# microbutton.net
KiCad netlist of a schematic drawn in EAGLE
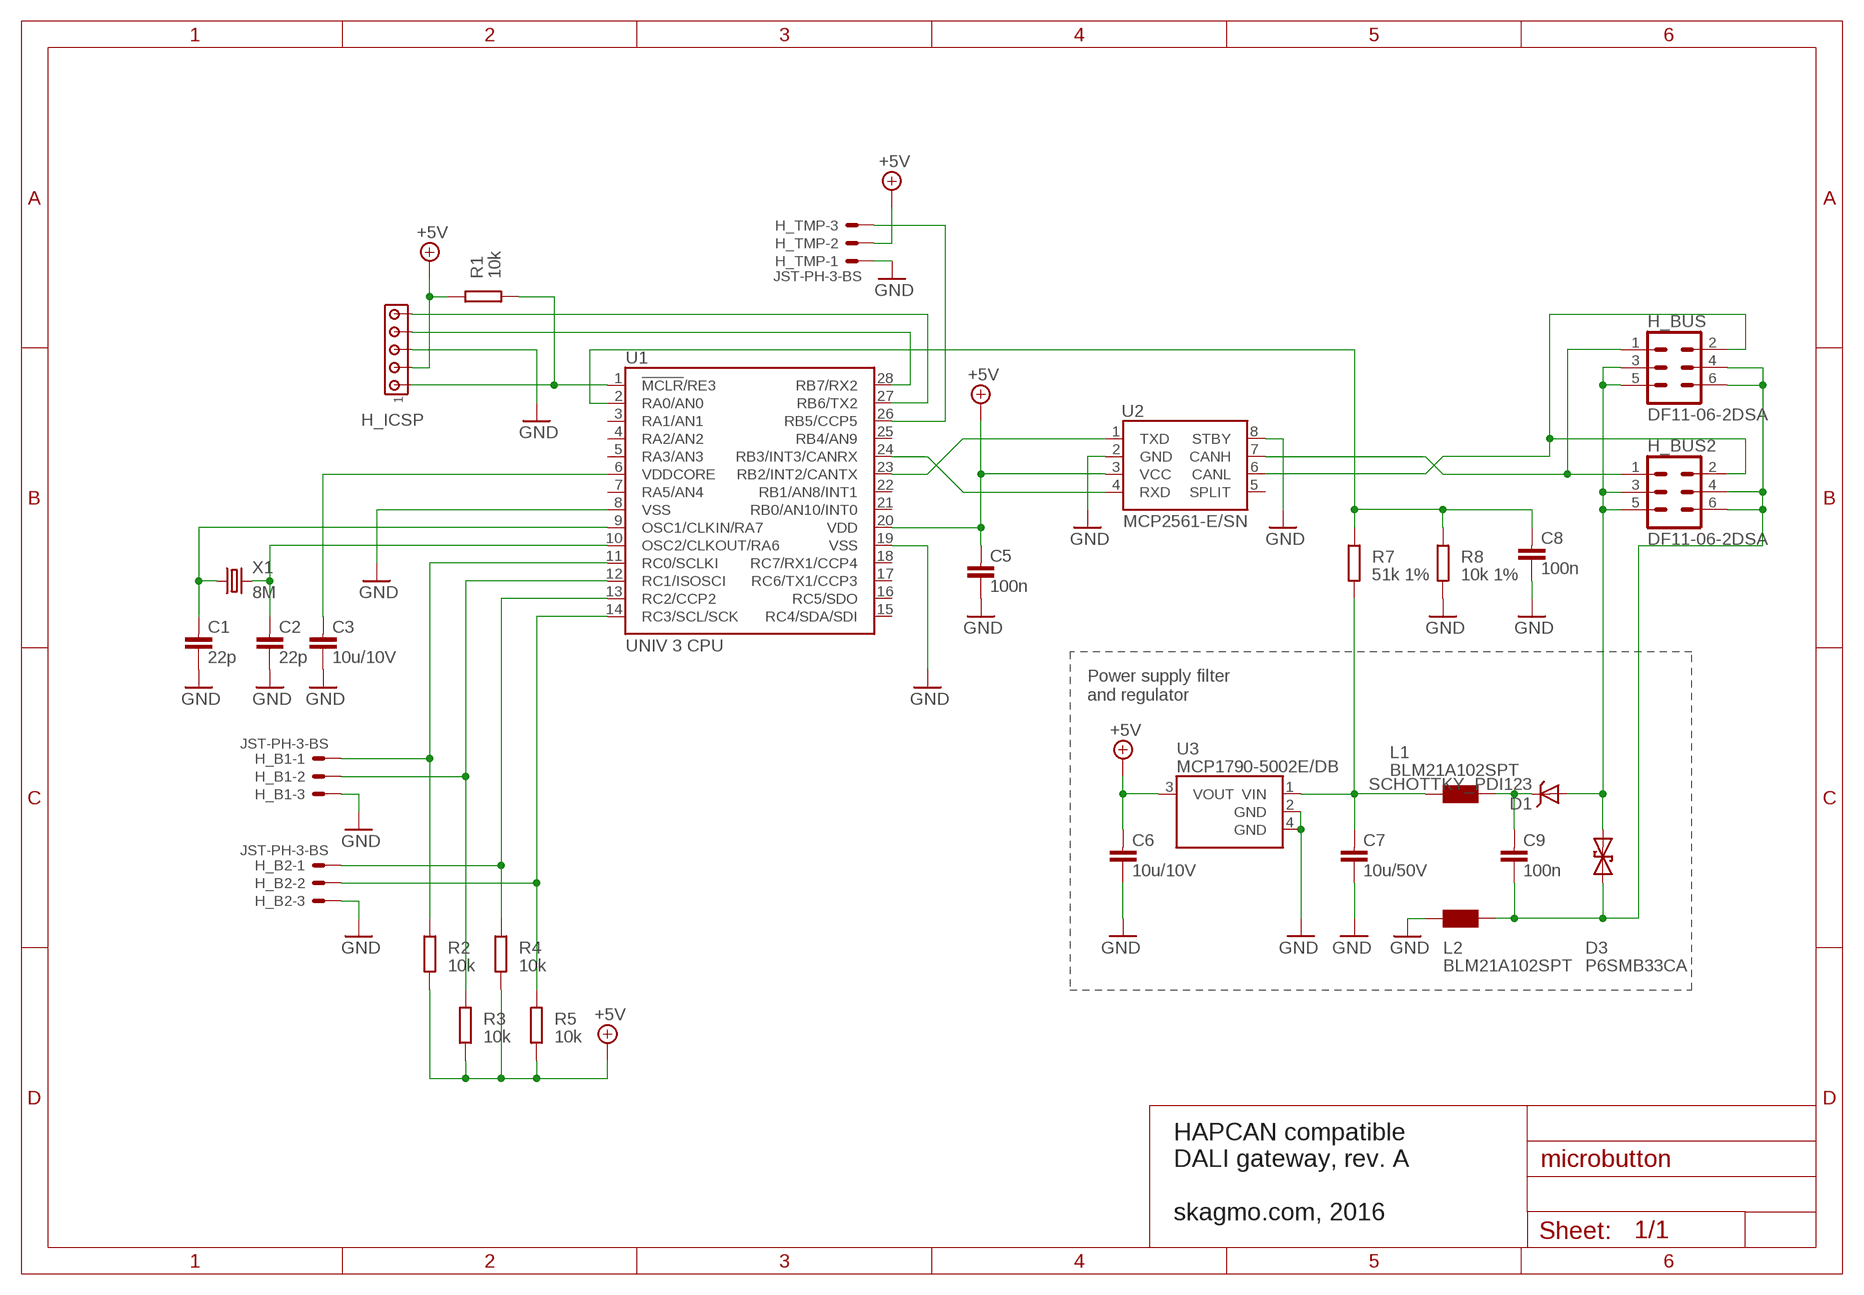
[diagram p0: schematic, sheet 1]

(export (version "E")
  (design (tool "Eeschema 10.0.6"))
  (components
    (comp (ref "C1")
      (value "22p")
      (footprint "eagle-import:0805")
      (libsource (lib "eagle-import") (part "CAPACITOR0805"))
    )
    (comp (ref "C2")
      (value "22p")
      (footprint "eagle-import:0805")
      (libsource (lib "eagle-import") (part "CAPACITOR0805"))
    )
    (comp (ref "C3")
      (value "10u/10V")
      (footprint "eagle-import:0805")
      (libsource (lib "eagle-import") (part "CAPACITOR0805"))
    )
    (comp (ref "C5")
      (value "100n")
      (footprint "eagle-import:0805")
      (libsource (lib "eagle-import") (part "CAPACITOR0805"))
    )
    (comp (ref "C6")
      (value "10u/10V")
      (footprint "eagle-import:0805")
      (libsource (lib "eagle-import") (part "CAPACITOR0805"))
    )
    (comp (ref "C7")
      (value "10u/50V")
      (footprint "eagle-import:1210")
      (libsource (lib "eagle-import") (part "CAPACITOR1210"))
    )
    (comp (ref "C8")
      (value "100n")
      (footprint "eagle-import:0805")
      (libsource (lib "eagle-import") (part "CAPACITOR0805"))
    )
    (comp (ref "C9")
      (value "100n")
      (footprint "eagle-import:0805")
      (libsource (lib "eagle-import") (part "CAPACITOR0805"))
    )
    (comp (ref "D1")
      (value "SCHOTTKY_PDI123")
      (footprint "eagle-import:POWERDI123")
      (libsource (lib "eagle-import") (part "SCHOTTKY_PDI123"))
    )
    (comp (ref "D3")
      (value "P6SMB33CA")
      (footprint "eagle-import:DO-214_TRANSIL2")
      (libsource (lib "eagle-import") (part "DIODE_TRANSIL2"))
    )
    (comp (ref "H_B1")
      (value "JST-PH-3-BS")
      (footprint "eagle-import:B3B-PH-K-S")
      (libsource (lib "eagle-import") (part "JST-PH-3-BS"))
    )
    (comp (ref "H_B2")
      (value "JST-PH-3-BS")
      (footprint "eagle-import:B3B-PH-K-S")
      (libsource (lib "eagle-import") (part "JST-PH-3-BS"))
    )
    (comp (ref "H_BUS")
      (value "DF11-06-2DSA")
      (footprint "eagle-import:DF11-06DP-2DSA")
      (libsource (lib "eagle-import") (part "DF11-06-2DSA"))
    )
    (comp (ref "H_BUS2")
      (value "DF11-06-2DSA")
      (footprint "eagle-import:DF11-06DP-2DSA")
      (libsource (lib "eagle-import") (part "DF11-06-2DSA"))
    )
    (comp (ref "H_ICSP")
      (value "HEADER5")
      (footprint "eagle-import:SIP-5")
      (libsource (lib "eagle-import") (part "HEADER5"))
    )
    (comp (ref "H_TMP")
      (value "JST-PH-3-BS")
      (footprint "eagle-import:B3B-PH-K-S")
      (libsource (lib "eagle-import") (part "JST-PH-3-BS"))
    )
    (comp (ref "L1")
      (value "BLM21A102SPT")
      (footprint "eagle-import:0805")
      (libsource (lib "eagle-import") (part "CHOKE0805"))
    )
    (comp (ref "L2")
      (value "BLM21A102SPT")
      (footprint "eagle-import:0805")
      (libsource (lib "eagle-import") (part "CHOKE0805"))
    )
    (comp (ref "R1")
      (value "10k")
      (footprint "eagle-import:0805")
      (libsource (lib "eagle-import") (part "RESISTOR0805"))
    )
    (comp (ref "R2")
      (value "10k")
      (footprint "eagle-import:0805")
      (libsource (lib "eagle-import") (part "RESISTOR0805"))
    )
    (comp (ref "R3")
      (value "10k")
      (footprint "eagle-import:0805")
      (libsource (lib "eagle-import") (part "RESISTOR0805"))
    )
    (comp (ref "R4")
      (value "10k")
      (footprint "eagle-import:0805")
      (libsource (lib "eagle-import") (part "RESISTOR0805"))
    )
    (comp (ref "R5")
      (value "10k")
      (footprint "eagle-import:0805")
      (libsource (lib "eagle-import") (part "RESISTOR0805"))
    )
    (comp (ref "R7")
      (value "51k 1%")
      (footprint "eagle-import:0805")
      (libsource (lib "eagle-import") (part "RESISTOR0805"))
    )
    (comp (ref "R8")
      (value "10k 1%")
      (footprint "eagle-import:0805")
      (libsource (lib "eagle-import") (part "RESISTOR0805"))
    )
    (comp (ref "U1")
      (value "UNIV 3 CPU")
      (footprint "eagle-import:UNIV3CPU")
      (libsource (lib "eagle-import") (part "UNIV3CPU"))
    )
    (comp (ref "U2")
      (value "MCP2561-E/SN")
      (footprint "eagle-import:SO-08")
      (libsource (lib "eagle-import") (part "MCP2561-E/SN"))
    )
    (comp (ref "U3")
      (value "MCP1790-5002E/DB")
      (footprint "eagle-import:SOT-223")
      (libsource (lib "eagle-import") (part "MCP1790"))
    )
    (comp (ref "X1")
      (value "8M")
      (footprint "eagle-import:TXC-7A")
      (libsource (lib "eagle-import") (part "CRYSTAL_TXC-7A"))
    )
  )
  (nets
    (net (code "1") (name "+5V") (class "Default")
      (node (ref "C5") (pin "1") (pinfunction "1_1") (pintype "passive"))
      (node (ref "C6") (pin "1") (pinfunction "1_1") (pintype "passive"))
      (node (ref "H_ICSP") (pin "2") (pinfunction "2_2") (pintype "passive"))
      (node (ref "H_TMP") (pin "2") (pinfunction "S_2") (pintype "passive"))
      (node (ref "R1") (pin "2") (pinfunction "2_2") (pintype "passive"))
      (node (ref "R2") (pin "1") (pinfunction "1_1") (pintype "passive"))
      (node (ref "R3") (pin "1") (pinfunction "1_1") (pintype "passive"))
      (node (ref "R4") (pin "1") (pinfunction "1_1") (pintype "passive"))
      (node (ref "R5") (pin "1") (pinfunction "1_1") (pintype "passive"))
      (node (ref "U1") (pin "20") (pinfunction "VDD_20") (pintype "bidirectional"))
      (node (ref "U2") (pin "3") (pinfunction "VCC_3") (pintype "bidirectional"))
      (node (ref "U3") (pin "3") (pinfunction "VOUT_3") (pintype "bidirectional"))
    )
    (net (code "2") (name "GND") (class "Default")
      (node (ref "C1") (pin "2") (pinfunction "2_2") (pintype "passive"))
      (node (ref "C2") (pin "2") (pinfunction "2_2") (pintype "passive"))
      (node (ref "C3") (pin "2") (pinfunction "2_2") (pintype "passive"))
      (node (ref "C5") (pin "2") (pinfunction "2_2") (pintype "passive"))
      (node (ref "C6") (pin "2") (pinfunction "2_2") (pintype "passive"))
      (node (ref "C7") (pin "2") (pinfunction "2_2") (pintype "passive"))
      (node (ref "C8") (pin "2") (pinfunction "2_2") (pintype "passive"))
      (node (ref "H_B1") (pin "3") (pinfunction "S_3") (pintype "passive"))
      (node (ref "H_B2") (pin "3") (pinfunction "S_3") (pintype "passive"))
      (node (ref "H_ICSP") (pin "3") (pinfunction "3_3") (pintype "passive"))
      (node (ref "H_TMP") (pin "1") (pinfunction "S_1") (pintype "passive"))
      (node (ref "L2") (pin "1") (pinfunction "1_1") (pintype "passive"))
      (node (ref "R8") (pin "1") (pinfunction "1_1") (pintype "passive"))
      (node (ref "U1") (pin "19") (pinfunction "VSS_19") (pintype "bidirectional"))
      (node (ref "U1") (pin "8") (pinfunction "VSS_8") (pintype "bidirectional"))
      (node (ref "U2") (pin "2") (pinfunction "GND_2") (pintype "bidirectional"))
      (node (ref "U2") (pin "8") (pinfunction "STBY_8") (pintype "bidirectional"))
      (node (ref "U3") (pin "2") (pinfunction "GND_2") (pintype "bidirectional"))
      (node (ref "U3") (pin "4") (pinfunction "GND_4") (pintype "bidirectional"))
    )
    (net (code "3") (name "Net-(C9-Pad1)") (class "Default")
      (node (ref "C9") (pin "1") (pinfunction "1_1") (pintype "passive"))
      (node (ref "D1") (pin "C") (pinfunction "C_C") (pintype "passive"))
      (node (ref "L1") (pin "2") (pinfunction "2_2") (pintype "passive"))
    )
    (net (code "4") (name "Net-(D3-1)") (class "Default")
      (node (ref "C9") (pin "2") (pinfunction "2_2") (pintype "passive"))
      (node (ref "D3") (pin "A") (pinfunction "1_A") (pintype "passive"))
      (node (ref "H_BUS") (pin "4") (pinfunction "4_4") (pintype "passive"))
      (node (ref "H_BUS") (pin "6") (pinfunction "6_6") (pintype "passive"))
      (node (ref "H_BUS2") (pin "4") (pinfunction "4_4") (pintype "passive"))
      (node (ref "H_BUS2") (pin "6") (pinfunction "6_6") (pintype "passive"))
      (node (ref "L2") (pin "2") (pinfunction "2_2") (pintype "passive"))
    )
    (net (code "5") (name "Net-(D3-2)") (class "Default")
      (node (ref "D1") (pin "A") (pinfunction "A_A") (pintype "passive"))
      (node (ref "D3") (pin "C") (pinfunction "2_C") (pintype "passive"))
      (node (ref "H_BUS") (pin "3") (pinfunction "3_3") (pintype "passive"))
      (node (ref "H_BUS") (pin "5") (pinfunction "5_5") (pintype "passive"))
      (node (ref "H_BUS2") (pin "3") (pinfunction "3_3") (pintype "passive"))
      (node (ref "H_BUS2") (pin "5") (pinfunction "5_5") (pintype "passive"))
    )
    (net (code "6") (name "Net-(H_B1A-S)") (class "Default")
      (node (ref "H_B1") (pin "1") (pinfunction "S_1") (pintype "passive"))
      (node (ref "R2") (pin "2") (pinfunction "2_2") (pintype "passive"))
      (node (ref "U1") (pin "11") (pinfunction "RC0/SCLKI_11") (pintype "bidirectional"))
    )
    (net (code "7") (name "Net-(H_B1B-S)") (class "Default")
      (node (ref "H_B1") (pin "2") (pinfunction "S_2") (pintype "passive"))
      (node (ref "R3") (pin "2") (pinfunction "2_2") (pintype "passive"))
      (node (ref "U1") (pin "12") (pinfunction "RC1/ISOSCI_12") (pintype "bidirectional"))
    )
    (net (code "8") (name "Net-(H_B2A-S)") (class "Default")
      (node (ref "H_B2") (pin "1") (pinfunction "S_1") (pintype "passive"))
      (node (ref "R4") (pin "2") (pinfunction "2_2") (pintype "passive"))
      (node (ref "U1") (pin "13") (pinfunction "RC2/CCP2_13") (pintype "bidirectional"))
    )
    (net (code "9") (name "Net-(H_B2B-S)") (class "Default")
      (node (ref "H_B2") (pin "2") (pinfunction "S_2") (pintype "passive"))
      (node (ref "R5") (pin "2") (pinfunction "2_2") (pintype "passive"))
      (node (ref "U1") (pin "14") (pinfunction "RC3/SCL/SCK_14") (pintype "bidirectional"))
    )
    (net (code "10") (name "Net-(H_TMPC-S)") (class "Default")
      (node (ref "H_TMP") (pin "3") (pinfunction "S_3") (pintype "passive"))
      (node (ref "U1") (pin "26") (pinfunction "RB5/CCP5_26") (pintype "bidirectional"))
    )
    (net (code "11") (name "Net-(U1-OSC1{slash}CLKIN{slash}RA7)") (class "Default")
      (node (ref "C1") (pin "1") (pinfunction "1_1") (pintype "passive"))
      (node (ref "U1") (pin "9") (pinfunction "OSC1/CLKIN/RA7_9") (pintype "bidirectional"))
      (node (ref "X1") (pin "1") (pinfunction "1_1") (pintype "passive"))
    )
    (net (code "12") (name "Net-(U1-OSC2{slash}CLKOUT{slash}RA6)") (class "Default")
      (node (ref "C2") (pin "1") (pinfunction "1_1") (pintype "passive"))
      (node (ref "U1") (pin "10") (pinfunction "OSC2/CLKOUT/RA6_10") (pintype "bidirectional"))
      (node (ref "X1") (pin "2") (pinfunction "2_2") (pintype "passive"))
    )
    (net (code "13") (name "Net-(U1-RA0{slash}AN0)") (class "Default")
      (node (ref "C8") (pin "1") (pinfunction "1_1") (pintype "passive"))
      (node (ref "R7") (pin "2") (pinfunction "2_2") (pintype "passive"))
      (node (ref "R8") (pin "2") (pinfunction "2_2") (pintype "passive"))
      (node (ref "U1") (pin "2") (pinfunction "RA0/AN0_2") (pintype "bidirectional"))
    )
    (net (code "14") (name "Net-(U1-RB2{slash}INT2{slash}CANTX)") (class "Default")
      (node (ref "U1") (pin "23") (pinfunction "RB2/INT2/CANTX_23") (pintype "bidirectional"))
      (node (ref "U2") (pin "1") (pinfunction "TXD_1") (pintype "bidirectional"))
    )
    (net (code "15") (name "Net-(U1-RB3{slash}INT3{slash}CANRX)") (class "Default")
      (node (ref "U1") (pin "24") (pinfunction "RB3/INT3/CANRX_24") (pintype "bidirectional"))
      (node (ref "U2") (pin "4") (pinfunction "RXD_4") (pintype "bidirectional"))
    )
    (net (code "16") (name "Net-(U1-RB6{slash}TX2)") (class "Default")
      (node (ref "H_ICSP") (pin "5") (pinfunction "5_5") (pintype "passive"))
      (node (ref "U1") (pin "27") (pinfunction "RB6/TX2_27") (pintype "bidirectional"))
    )
    (net (code "17") (name "Net-(U1-RB7{slash}RX2)") (class "Default")
      (node (ref "H_ICSP") (pin "4") (pinfunction "4_4") (pintype "passive"))
      (node (ref "U1") (pin "28") (pinfunction "RB7/RX2_28") (pintype "bidirectional"))
    )
    (net (code "18") (name "Net-(U1-VDDCORE)") (class "Default")
      (node (ref "C3") (pin "1") (pinfunction "1_1") (pintype "passive"))
      (node (ref "U1") (pin "6") (pinfunction "VDDCORE_6") (pintype "bidirectional"))
    )
    (net (code "19") (name "Net-(U1-~{MCLR}{slash}RE3)") (class "Default")
      (node (ref "H_ICSP") (pin "1") (pinfunction "1_1") (pintype "passive"))
      (node (ref "R1") (pin "1") (pinfunction "1_1") (pintype "passive"))
      (node (ref "U1") (pin "1") (pinfunction "~{MCLR}/RE3_1") (pintype "bidirectional"))
    )
    (net (code "20") (name "Net-(U2-CANH)") (class "Default")
      (node (ref "H_BUS") (pin "1") (pinfunction "1_1") (pintype "passive"))
      (node (ref "H_BUS2") (pin "1") (pinfunction "1_1") (pintype "passive"))
      (node (ref "U2") (pin "7") (pinfunction "CANH_7") (pintype "bidirectional"))
    )
    (net (code "21") (name "Net-(U2-CANL)") (class "Default")
      (node (ref "H_BUS") (pin "2") (pinfunction "2_2") (pintype "passive"))
      (node (ref "H_BUS2") (pin "2") (pinfunction "2_2") (pintype "passive"))
      (node (ref "U2") (pin "6") (pinfunction "CANL_6") (pintype "bidirectional"))
    )
    (net (code "22") (name "Net-(U3-VIN)") (class "Default")
      (node (ref "C7") (pin "1") (pinfunction "1_1") (pintype "passive"))
      (node (ref "L1") (pin "1") (pinfunction "1_1") (pintype "passive"))
      (node (ref "R7") (pin "1") (pinfunction "1_1") (pintype "passive"))
      (node (ref "U3") (pin "1") (pinfunction "VIN_1") (pintype "bidirectional"))
    )
    (net (code "23") (name "unconnected-(U1-RA1{slash}AN1-Pad3)") (class "Default")
      (node (ref "U1") (pin "3") (pinfunction "RA1/AN1_3") (pintype "bidirectional"))
    )
    (net (code "24") (name "unconnected-(U1-RA2{slash}AN2-Pad4)") (class "Default")
      (node (ref "U1") (pin "4") (pinfunction "RA2/AN2_4") (pintype "bidirectional"))
    )
    (net (code "25") (name "unconnected-(U1-RA3{slash}AN3-Pad5)") (class "Default")
      (node (ref "U1") (pin "5") (pinfunction "RA3/AN3_5") (pintype "bidirectional"))
    )
    (net (code "26") (name "unconnected-(U1-RA5{slash}AN4-Pad7)") (class "Default")
      (node (ref "U1") (pin "7") (pinfunction "RA5/AN4_7") (pintype "bidirectional"))
    )
    (net (code "27") (name "unconnected-(U1-RB0{slash}AN10{slash}INT0-Pad21)") (class "Default")
      (node (ref "U1") (pin "21") (pinfunction "RB0/AN10/INT0_21") (pintype "bidirectional"))
    )
    (net (code "28") (name "unconnected-(U1-RB1{slash}AN8{slash}INT1-Pad22)") (class "Default")
      (node (ref "U1") (pin "22") (pinfunction "RB1/AN8/INT1_22") (pintype "bidirectional"))
    )
    (net (code "29") (name "unconnected-(U1-RB4{slash}AN9-Pad25)") (class "Default")
      (node (ref "U1") (pin "25") (pinfunction "RB4/AN9_25") (pintype "bidirectional"))
    )
    (net (code "30") (name "unconnected-(U1-RC4{slash}SDA{slash}SDI-Pad15)") (class "Default")
      (node (ref "U1") (pin "15") (pinfunction "RC4/SDA/SDI_15") (pintype "bidirectional"))
    )
    (net (code "31") (name "unconnected-(U1-RC5{slash}SDO-Pad16)") (class "Default")
      (node (ref "U1") (pin "16") (pinfunction "RC5/SDO_16") (pintype "bidirectional"))
    )
    (net (code "32") (name "unconnected-(U1-RC6{slash}TX1{slash}CCP3-Pad17)") (class "Default")
      (node (ref "U1") (pin "17") (pinfunction "RC6/TX1/CCP3_17") (pintype "bidirectional"))
    )
    (net (code "33") (name "unconnected-(U1-RC7{slash}RX1{slash}CCP4-Pad18)") (class "Default")
      (node (ref "U1") (pin "18") (pinfunction "RC7/RX1/CCP4_18") (pintype "bidirectional"))
    )
    (net (code "34") (name "unconnected-(U2-SPLIT-Pad5)") (class "Default")
      (node (ref "U2") (pin "5") (pinfunction "SPLIT_5") (pintype "bidirectional"))
    )
  )
)
